# circuit.net
KiCad netlist of a schematic drawn in EAGLE
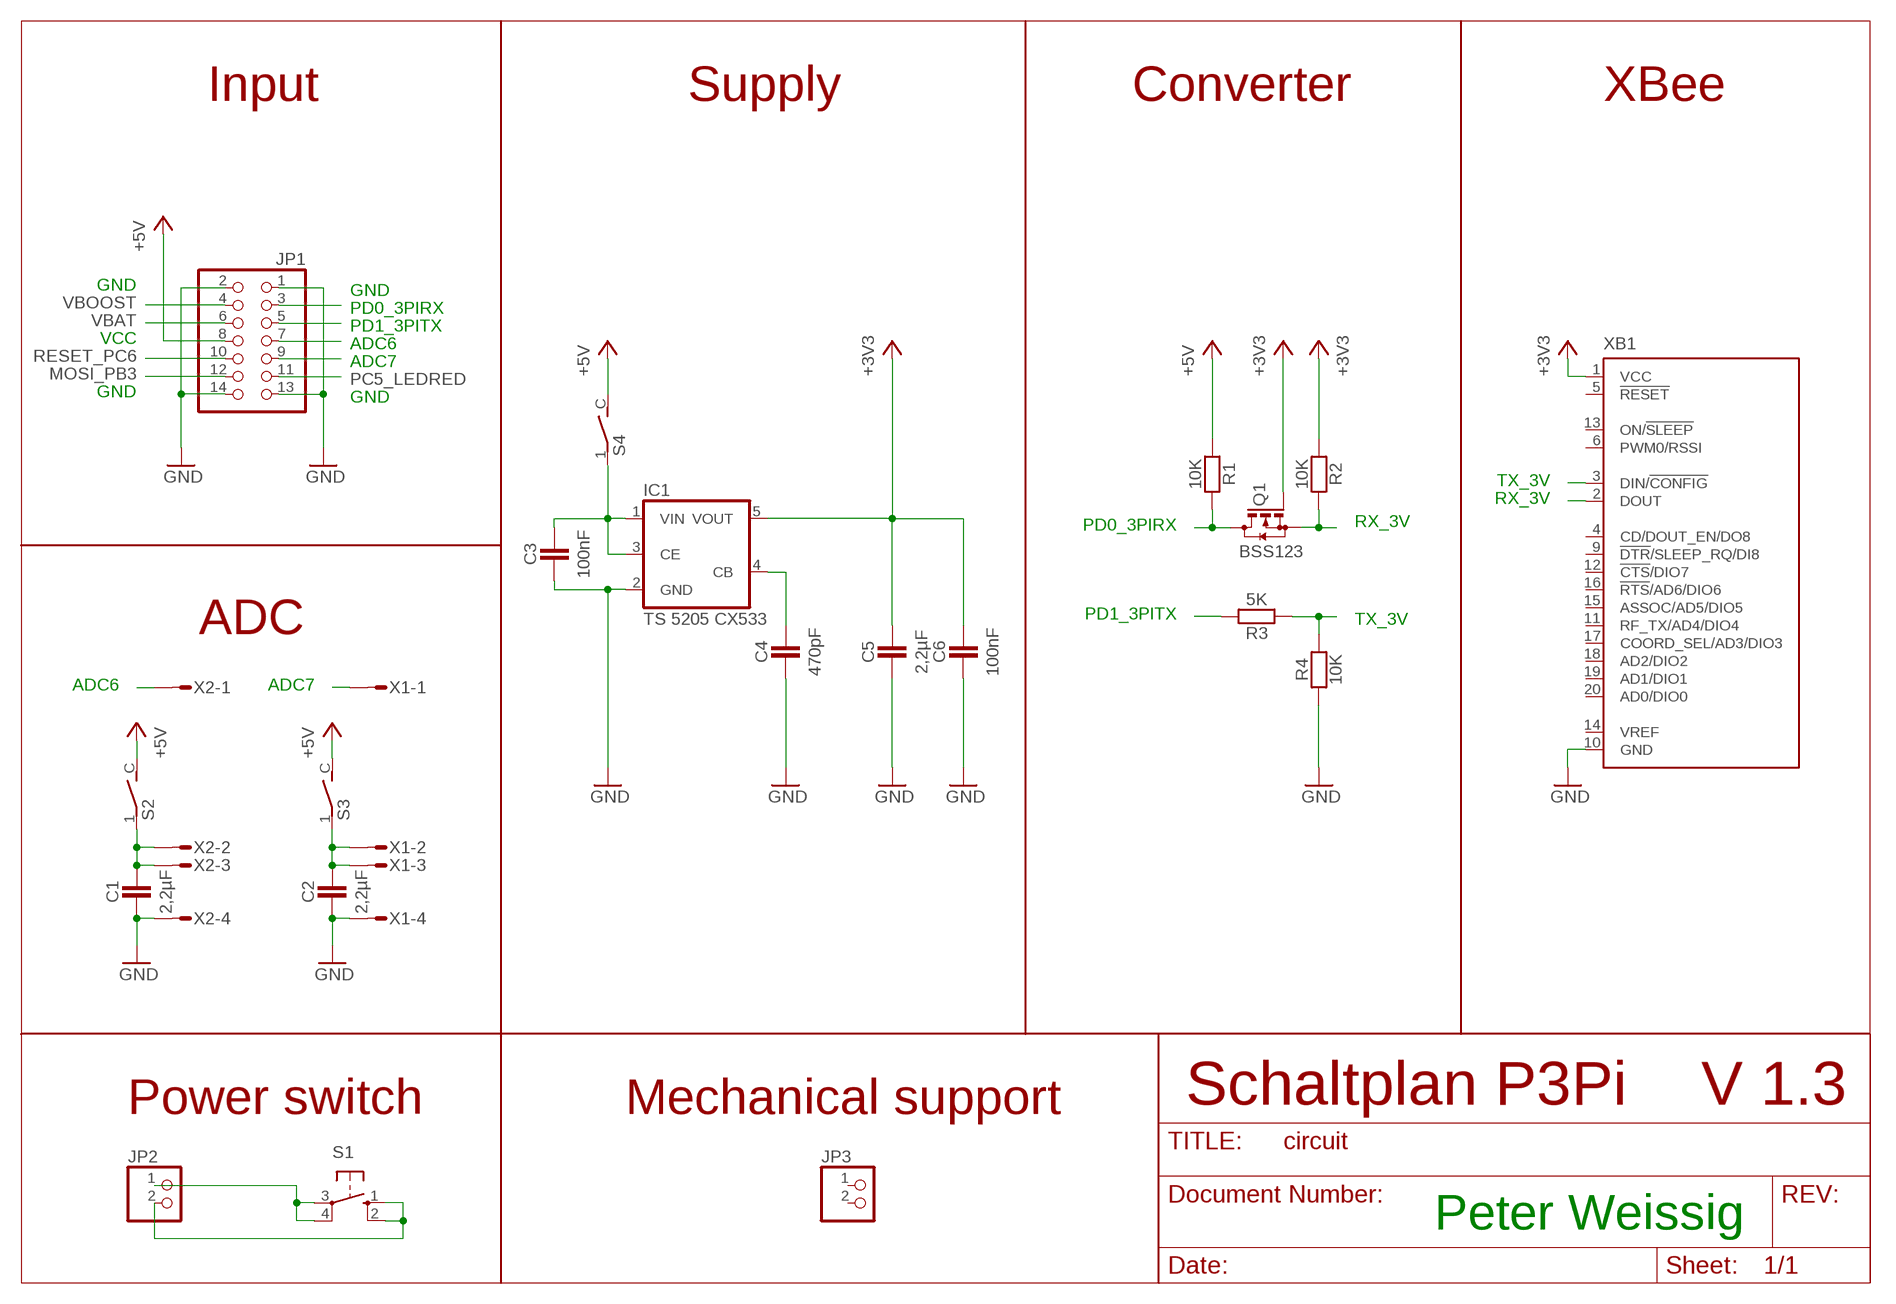
[diagram p0: schematic, sheet 1]

(export (version "E")
  (design (tool "Eeschema 10.0.6"))
  (components
    (comp (ref "C1")
      (value "2,2µF")
      (footprint "eagle-import:SMD_1206")
      (libsource (lib "eagle-import") (part "CAPACITATOR-1206"))
    )
    (comp (ref "C2")
      (value "2,2µF")
      (footprint "eagle-import:SMD_1206")
      (libsource (lib "eagle-import") (part "CAPACITATOR-1206"))
    )
    (comp (ref "C3")
      (value "100nF")
      (footprint "eagle-import:SMD_1206")
      (libsource (lib "eagle-import") (part "CAPACITATOR-1206"))
    )
    (comp (ref "C4")
      (value "470pF")
      (footprint "eagle-import:SMD_1206")
      (libsource (lib "eagle-import") (part "CAPACITATOR-1206"))
    )
    (comp (ref "C5")
      (value "2,2µF")
      (footprint "eagle-import:SMD_1206")
      (libsource (lib "eagle-import") (part "CAPACITATOR-1206"))
    )
    (comp (ref "C6")
      (value "100nF")
      (footprint "eagle-import:SMD_1206")
      (libsource (lib "eagle-import") (part "CAPACITATOR-1206"))
    )
    (comp (ref "IC1")
      (value "TS 5205 CX533")
      (footprint "eagle-import:SOT25")
      (libsource (lib "eagle-import") (part "TS520533"))
    )
    (comp (ref "JP1")
      (value "PINHD-2X7")
      (footprint "eagle-import:2X07")
      (libsource (lib "eagle-import") (part "PINHD-2X7"))
    )
    (comp (ref "JP2")
      (value "PINHD-1X2")
      (footprint "eagle-import:1X02")
      (libsource (lib "eagle-import") (part "PINHD-1X2"))
    )
    (comp (ref "JP3")
      (value "PINHD-1X2")
      (footprint "eagle-import:1X02")
      (libsource (lib "eagle-import") (part "PINHD-1X2"))
    )
    (comp (ref "Q1")
      (value "BSS123")
      (footprint "eagle-import:SOT23")
      (libsource (lib "eagle-import") (part "BSS123"))
    )
    (comp (ref "R1")
      (value "10K")
      (footprint "eagle-import:SMD_1206")
      (libsource (lib "eagle-import") (part "RESISTOR-1206"))
    )
    (comp (ref "R2")
      (value "10K")
      (footprint "eagle-import:SMD_1206")
      (libsource (lib "eagle-import") (part "RESISTOR-1206"))
    )
    (comp (ref "R3")
      (value "5K")
      (footprint "eagle-import:SMD_1206")
      (libsource (lib "eagle-import") (part "RESISTOR-1206"))
    )
    (comp (ref "R4")
      (value "10K")
      (footprint "eagle-import:SMD_1206")
      (libsource (lib "eagle-import") (part "RESISTOR-1206"))
    )
    (comp (ref "S1")
      (value "TASTER")
      (footprint "eagle-import:TASTER_SMD")
      (libsource (lib "eagle-import") (part "TASTER"))
    )
    (comp (ref "S2")
      (value "SCHALTER")
      (footprint "eagle-import:SCHALTER_SMD")
      (libsource (lib "eagle-import") (part "SCHALTER"))
    )
    (comp (ref "S3")
      (value "SCHALTER")
      (footprint "eagle-import:SCHALTER_SMD")
      (libsource (lib "eagle-import") (part "SCHALTER"))
    )
    (comp (ref "S4")
      (value "SCHALTER")
      (footprint "eagle-import:SCHALTER_SMD")
      (libsource (lib "eagle-import") (part "SCHALTER"))
    )
    (comp (ref "X1")
      (value "STECKER_MICROMATCH_4SMD")
      (footprint "eagle-import:STECKER_MICROMATCH_4SMD")
      (libsource (lib "eagle-import") (part "STECKER_MICROMATCH_4SMD"))
    )
    (comp (ref "X2")
      (value "STECKER_MICROMATCH_4SMD")
      (footprint "eagle-import:STECKER_MICROMATCH_4SMD")
      (libsource (lib "eagle-import") (part "STECKER_MICROMATCH_4SMD"))
    )
    (comp (ref "XB1")
      (value "XBEESMD")
      (footprint "eagle-import:FUNK_XBEE_SMD")
      (libsource (lib "eagle-import") (part "XBEESMD"))
    )
  )
  (nets
    (net (code "1") (name "+3V3") (class "Default")
      (node (ref "C5") (pin "1") (pinfunction "1_1") (pintype "passive"))
      (node (ref "C6") (pin "1") (pinfunction "1_1") (pintype "passive"))
      (node (ref "IC1") (pin "5") (pinfunction "VOUT_5") (pintype "passive"))
      (node (ref "Q1") (pin "1") (pinfunction "G_1") (pintype "passive"))
      (node (ref "R2") (pin "2") (pinfunction "P2_2") (pintype "passive"))
      (node (ref "XB1") (pin "1") (pinfunction "VCC_1") (pintype "power_in"))
    )
    (net (code "2") (name "+5V") (class "Default")
      (node (ref "JP1") (pin "8") (pinfunction "8_8") (pintype "passive"))
      (node (ref "R1") (pin "2") (pinfunction "P2_2") (pintype "passive"))
      (node (ref "S2") (pin "C") (pinfunction "2_C") (pintype "passive"))
      (node (ref "S3") (pin "C") (pinfunction "2_C") (pintype "passive"))
      (node (ref "S4") (pin "C") (pinfunction "2_C") (pintype "passive"))
    )
    (net (code "3") (name "/ADC6") (class "Default")
      (node (ref "JP1") (pin "7") (pinfunction "7_7") (pintype "passive"))
      (node (ref "X2") (pin "1") (pinfunction "S_1") (pintype "passive"))
    )
    (net (code "4") (name "/ADC7") (class "Default")
      (node (ref "JP1") (pin "9") (pinfunction "9_9") (pintype "passive"))
      (node (ref "X1") (pin "1") (pinfunction "S_1") (pintype "passive"))
    )
    (net (code "5") (name "/MOSI_PB3") (class "Default")
      (node (ref "JP1") (pin "12") (pinfunction "12_12") (pintype "passive"))
    )
    (net (code "6") (name "/PC5_LEDRED") (class "Default")
      (node (ref "JP1") (pin "11") (pinfunction "11_11") (pintype "passive"))
    )
    (net (code "7") (name "/PD0_3PIRX") (class "Default")
      (node (ref "JP1") (pin "3") (pinfunction "3_3") (pintype "passive"))
      (node (ref "Q1") (pin "3") (pinfunction "D_3") (pintype "passive"))
      (node (ref "R1") (pin "1") (pinfunction "P1_1") (pintype "passive"))
    )
    (net (code "8") (name "/PD1_3PITX") (class "Default")
      (node (ref "JP1") (pin "5") (pinfunction "5_5") (pintype "passive"))
      (node (ref "R3") (pin "1") (pinfunction "P1_1") (pintype "passive"))
    )
    (net (code "9") (name "/RESET_PC6") (class "Default")
      (node (ref "JP1") (pin "10") (pinfunction "10_10") (pintype "passive"))
    )
    (net (code "10") (name "/RX_3V") (class "Default")
      (node (ref "Q1") (pin "2") (pinfunction "S_2") (pintype "passive"))
      (node (ref "R2") (pin "1") (pinfunction "P1_1") (pintype "passive"))
      (node (ref "XB1") (pin "2") (pinfunction "DOUT_2") (pintype "output"))
    )
    (net (code "11") (name "/TX_3V") (class "Default")
      (node (ref "R3") (pin "2") (pinfunction "P2_2") (pintype "passive"))
      (node (ref "R4") (pin "1") (pinfunction "P1_1") (pintype "passive"))
      (node (ref "XB1") (pin "3") (pinfunction "DIN/~{CONFIG}_3") (pintype "input"))
    )
    (net (code "12") (name "/VBAT") (class "Default")
      (node (ref "JP1") (pin "6") (pinfunction "6_6") (pintype "passive"))
    )
    (net (code "13") (name "/VBOOST") (class "Default")
      (node (ref "JP1") (pin "4") (pinfunction "4_4") (pintype "passive"))
    )
    (net (code "14") (name "GND") (class "Default")
      (node (ref "C1") (pin "2") (pinfunction "2_2") (pintype "passive"))
      (node (ref "C2") (pin "2") (pinfunction "2_2") (pintype "passive"))
      (node (ref "C3") (pin "2") (pinfunction "2_2") (pintype "passive"))
      (node (ref "C4") (pin "2") (pinfunction "2_2") (pintype "passive"))
      (node (ref "C5") (pin "2") (pinfunction "2_2") (pintype "passive"))
      (node (ref "C6") (pin "2") (pinfunction "2_2") (pintype "passive"))
      (node (ref "IC1") (pin "2") (pinfunction "GND_2") (pintype "passive"))
      (node (ref "JP1") (pin "1") (pinfunction "1_1") (pintype "passive"))
      (node (ref "JP1") (pin "13") (pinfunction "13_13") (pintype "passive"))
      (node (ref "JP1") (pin "14") (pinfunction "14_14") (pintype "passive"))
      (node (ref "JP1") (pin "2") (pinfunction "2_2") (pintype "passive"))
      (node (ref "R4") (pin "2") (pinfunction "P2_2") (pintype "passive"))
      (node (ref "X1") (pin "4") (pinfunction "S_4") (pintype "passive"))
      (node (ref "X2") (pin "4") (pinfunction "S_4") (pintype "passive"))
      (node (ref "XB1") (pin "10") (pinfunction "GND_10") (pintype "power_in"))
    )
    (net (code "15") (name "Net-(IC1-CB)") (class "Default")
      (node (ref "C4") (pin "1") (pinfunction "1_1") (pintype "passive"))
      (node (ref "IC1") (pin "4") (pinfunction "CB_4") (pintype "input"))
    )
    (net (code "16") (name "Net-(IC1-CE)") (class "Default")
      (node (ref "C3") (pin "1") (pinfunction "1_1") (pintype "passive"))
      (node (ref "IC1") (pin "1") (pinfunction "VIN_1") (pintype "input"))
      (node (ref "IC1") (pin "3") (pinfunction "CE_3") (pintype "input"))
      (node (ref "S4") (pin "1") (pinfunction "1_1") (pintype "passive"))
    )
    (net (code "17") (name "Net-(S1-P)") (class "Default")
      (node (ref "JP2") (pin "1") (pinfunction "1_1") (pintype "passive"))
      (node (ref "S1") (pin "3") (pinfunction "P_3") (pintype "passive"))
      (node (ref "S1") (pin "4") (pinfunction "P1_4") (pintype "passive"))
    )
    (net (code "18") (name "Net-(S1-S)") (class "Default")
      (node (ref "JP2") (pin "2") (pinfunction "2_2") (pintype "passive"))
      (node (ref "S1") (pin "1") (pinfunction "S_1") (pintype "passive"))
      (node (ref "S1") (pin "2") (pinfunction "S1_2") (pintype "passive"))
    )
    (net (code "19") (name "Net-(X1B-S)") (class "Default")
      (node (ref "C2") (pin "1") (pinfunction "1_1") (pintype "passive"))
      (node (ref "S3") (pin "1") (pinfunction "1_1") (pintype "passive"))
      (node (ref "X1") (pin "2") (pinfunction "S_2") (pintype "passive"))
      (node (ref "X1") (pin "3") (pinfunction "S_3") (pintype "passive"))
    )
    (net (code "20") (name "Net-(X2B-S)") (class "Default")
      (node (ref "C1") (pin "1") (pinfunction "1_1") (pintype "passive"))
      (node (ref "S2") (pin "1") (pinfunction "1_1") (pintype "passive"))
      (node (ref "X2") (pin "2") (pinfunction "S_2") (pintype "passive"))
      (node (ref "X2") (pin "3") (pinfunction "S_3") (pintype "passive"))
    )
    (net (code "21") (name "unconnected-(JP3-Pad1)") (class "Default")
      (node (ref "JP3") (pin "1") (pinfunction "1_1") (pintype "passive"))
    )
    (net (code "22") (name "unconnected-(JP3-Pad2)") (class "Default")
      (node (ref "JP3") (pin "2") (pinfunction "2_2") (pintype "passive"))
    )
    (net (code "23") (name "unconnected-(XB1-AD0{slash}DIO0-Pad20)") (class "Default")
      (node (ref "XB1") (pin "20") (pinfunction "AD0/DIO0_20") (pintype "bidirectional"))
    )
    (net (code "24") (name "unconnected-(XB1-AD1{slash}DIO1-Pad19)") (class "Default")
      (node (ref "XB1") (pin "19") (pinfunction "AD1/DIO1_19") (pintype "bidirectional"))
    )
    (net (code "25") (name "unconnected-(XB1-AD2{slash}DIO2-Pad18)") (class "Default")
      (node (ref "XB1") (pin "18") (pinfunction "AD2/DIO2_18") (pintype "bidirectional"))
    )
    (net (code "26") (name "unconnected-(XB1-ASSOC{slash}AD5{slash}DIO5-Pad15)") (class "Default")
      (node (ref "XB1") (pin "15") (pinfunction "ASSOC/AD5/DIO5_15") (pintype "bidirectional"))
    )
    (net (code "27") (name "unconnected-(XB1-CD{slash}DOUT_EN{slash}DO8-Pad4)") (class "Default")
      (node (ref "XB1") (pin "4") (pinfunction "CD/DOUT_EN/DO8_4") (pintype "output"))
    )
    (net (code "28") (name "unconnected-(XB1-COORD_SEL{slash}AD3{slash}DIO3-Pad17)") (class "Default")
      (node (ref "XB1") (pin "17") (pinfunction "COORD_SEL/AD3/DIO3_17") (pintype "bidirectional"))
    )
    (net (code "29") (name "unconnected-(XB1-ON{slash}~{SLEEP}-Pad13)") (class "Default")
      (node (ref "XB1") (pin "13") (pinfunction "ON/~{SLEEP}_13") (pintype "output"))
    )
    (net (code "30") (name "unconnected-(XB1-PWM0{slash}RSSI-Pad6)") (class "Default")
      (node (ref "XB1") (pin "6") (pinfunction "PWM0/RSSI_6") (pintype "output"))
    )
    (net (code "31") (name "unconnected-(XB1-RF_TX{slash}AD4{slash}DIO4-Pad11)") (class "Default")
      (node (ref "XB1") (pin "11") (pinfunction "RF_TX/AD4/DIO4_11") (pintype "bidirectional"))
    )
    (net (code "32") (name "unconnected-(XB1-VREF-Pad14)") (class "Default")
      (node (ref "XB1") (pin "14") (pinfunction "VREF_14") (pintype "input"))
    )
    (net (code "33") (name "unconnected-(XB1-~{CTS}{slash}DIO7-Pad12)") (class "Default")
      (node (ref "XB1") (pin "12") (pinfunction "~{CTS}/DIO7_12") (pintype "bidirectional"))
    )
    (net (code "34") (name "unconnected-(XB1-~{DTR}{slash}SLEEP_RQ{slash}DI8-Pad9)") (class "Default")
      (node (ref "XB1") (pin "9") (pinfunction "~{DTR}/SLEEP_RQ/DI8_9") (pintype "bidirectional"))
    )
    (net (code "35") (name "unconnected-(XB1-~{RESET}-Pad5)") (class "Default")
      (node (ref "XB1") (pin "5") (pinfunction "~{RESET}_5") (pintype "input"))
    )
    (net (code "36") (name "unconnected-(XB1-~{RTS}{slash}AD6{slash}DIO6-Pad16)") (class "Default")
      (node (ref "XB1") (pin "16") (pinfunction "~{RTS}/AD6/DIO6_16") (pintype "bidirectional"))
    )
  )
)
